# OpenTracker_GPS.net
KiCad netlist of a schematic drawn in EAGLE
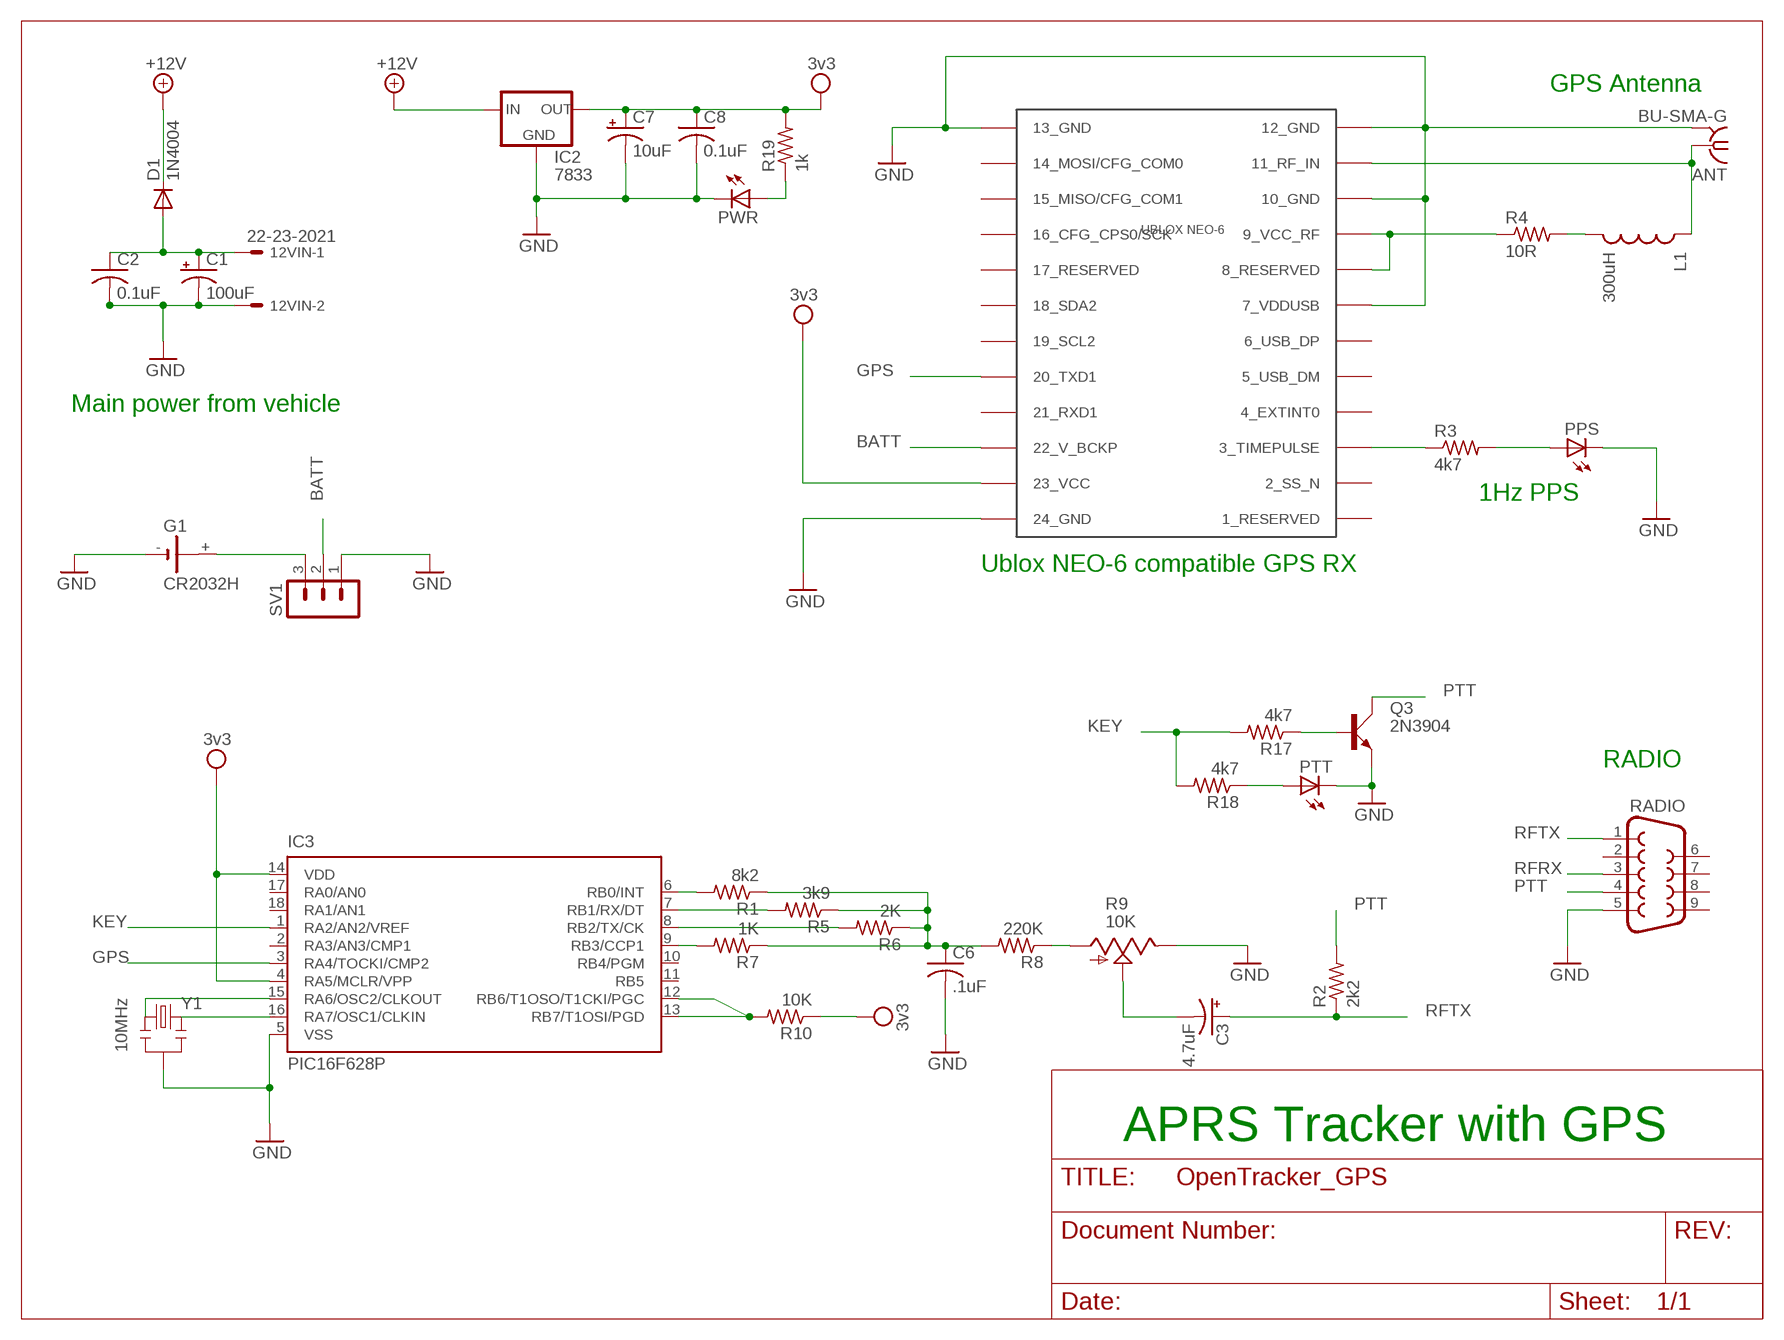
[diagram p0: schematic, sheet 1]

(export (version "E")
  (design (tool "Eeschema 10.0.6"))
  (components
    (comp (ref "12VIN")
      (value "22-23-2021")
      (footprint "eagle-import:22-23-2021")
      (fields (field (name "MF") "MOLEX"))
      (libsource (lib "eagle-import") (part "22-23-2021"))
    )
    (comp (ref "ANT")
      (value "BU-SMA-G")
      (footprint "eagle-import:BU-SMA-G")
      (libsource (lib "eagle-import") (part "BU-SMA-G"))
    )
    (comp (ref "C1")
      (value "100uF")
      (footprint "eagle-import:CPOL-RADIAL-10UF-25V")
      (libsource (lib "eagle-import") (part "CAP_POLPTH2"))
    )
    (comp (ref "C2")
      (value "0.1uF")
      (footprint "eagle-import:C025-025X050")
      (libsource (lib "eagle-import") (part "C-US025-025X050"))
    )
    (comp (ref "C3")
      (value "4.7uF")
      (footprint "eagle-import:CPOL-RADIAL-10UF-25V")
      (libsource (lib "eagle-import") (part "CAP_POLPTH2"))
    )
    (comp (ref "C6")
      (value ".1uF")
      (footprint "eagle-import:C025-025X050")
      (libsource (lib "eagle-import") (part "C-US025-025X050"))
    )
    (comp (ref "C7")
      (value "10uF")
      (footprint "eagle-import:CPOL-RADIAL-10UF-25V")
      (libsource (lib "eagle-import") (part "CAP_POLPTH2"))
    )
    (comp (ref "C8")
      (value "0.1uF")
      (footprint "eagle-import:C025-025X050")
      (libsource (lib "eagle-import") (part "C-US025-025X050"))
    )
    (comp (ref "D1")
      (value "1N4004")
      (footprint "eagle-import:DO41-10")
      (libsource (lib "eagle-import") (part "1N4004"))
    )
    (comp (ref "G1")
      (value "CR2032H")
      (footprint "eagle-import:CR2032H")
      (libsource (lib "eagle-import") (part "CR2032H"))
    )
    (comp (ref "IC2")
      (value "7833")
      (footprint "eagle-import:TO-220-ALT")
      (libsource (lib "eagle-import") (part "V_REG_78XX-TO-220"))
    )
    (comp (ref "IC3")
      (value "PIC16F628P")
      (footprint "eagle-import:DIL18")
      (libsource (lib "eagle-import") (part "PIC16F62P8"))
    )
    (comp (ref "L1")
      (value "300uH")
      (footprint "eagle-import:0805")
      (libsource (lib "eagle-import") (part "INDUCTOR0805"))
    )
    (comp (ref "PPS")
      (value "LED0603")
      (footprint "eagle-import:LED-0603")
      (libsource (lib "eagle-import") (part "LED0603"))
    )
    (comp (ref "PTT")
      (value "LED3MM")
      (footprint "eagle-import:LED3MM")
      (libsource (lib "eagle-import") (part "LED3MM"))
    )
    (comp (ref "PWR")
      (value "LED3MM")
      (footprint "eagle-import:LED3MM")
      (libsource (lib "eagle-import") (part "LED3MM"))
    )
    (comp (ref "Q3")
      (value "2N3904")
      (footprint "eagle-import:TO92D")
      (libsource (lib "eagle-import") (part "2N3904"))
    )
    (comp (ref "R1")
      (value "8k2")
      (footprint "eagle-import:0207_2V")
      (libsource (lib "eagle-import") (part "R-US_0207/2V"))
    )
    (comp (ref "R2")
      (value "2k2")
      (footprint "eagle-import:0207_2V")
      (libsource (lib "eagle-import") (part "R-US_0207/2V"))
    )
    (comp (ref "R3")
      (value "4k7")
      (footprint "eagle-import:M0805")
      (libsource (lib "eagle-import") (part "R-US_M0805"))
    )
    (comp (ref "R4")
      (value "10R")
      (footprint "eagle-import:M0805")
      (libsource (lib "eagle-import") (part "R-US_M0805"))
    )
    (comp (ref "R5")
      (value "3k9")
      (footprint "eagle-import:0207_2V")
      (libsource (lib "eagle-import") (part "R-US_0207/2V"))
    )
    (comp (ref "R6")
      (value "2K")
      (footprint "eagle-import:0207_2V")
      (libsource (lib "eagle-import") (part "R-US_0207/2V"))
    )
    (comp (ref "R7")
      (value "1K")
      (footprint "eagle-import:0207_2V")
      (libsource (lib "eagle-import") (part "R-US_0207/2V"))
    )
    (comp (ref "R8")
      (value "220K")
      (footprint "eagle-import:0207_2V")
      (libsource (lib "eagle-import") (part "R-US_0207/2V"))
    )
    (comp (ref "R9")
      (value "10K")
      (footprint "eagle-import:CA6V")
      (libsource (lib "eagle-import") (part "TRIM_US-CA6V"))
    )
    (comp (ref "R10")
      (value "10K")
      (footprint "eagle-import:0207_2V")
      (libsource (lib "eagle-import") (part "R-US_0207/2V"))
    )
    (comp (ref "R17")
      (value "4k7")
      (footprint "eagle-import:0207_2V")
      (libsource (lib "eagle-import") (part "R-US_0207/2V"))
    )
    (comp (ref "R18")
      (value "4k7")
      (footprint "eagle-import:0207_2V")
      (libsource (lib "eagle-import") (part "R-US_0207/2V"))
    )
    (comp (ref "R19")
      (value "1k")
      (footprint "eagle-import:0207_2V")
      (libsource (lib "eagle-import") (part "R-US_0207/2V"))
    )
    (comp (ref "RADIO")
      (value "F09HP")
      (footprint "eagle-import:F09HP")
      (libsource (lib "eagle-import") (part "F09HP"))
    )
    (comp (ref "SV1")
      (value "MA03-1")
      (footprint "eagle-import:MA03-1")
      (libsource (lib "eagle-import") (part "MA03-1"))
    )
    (comp (ref "U$1")
      (value "UBLOX_NEO-6")
      (footprint "eagle-import:UBLOX_NEO-6P")
      (libsource (lib "eagle-import") (part "UBLOX_NEO-6"))
    )
    (comp (ref "Y1")
      (value "10MHz")
      (footprint "eagle-import:RESONATOR-PTH")
      (libsource (lib "eagle-import") (part "RESONATORPTH"))
    )
  )
  (nets
    (net (code "1") (name "+12V") (class "Default")
      (node (ref "D1") (pin "C") (pinfunction "C_C") (pintype "passive"))
      (node (ref "IC2") (pin "IN") (pinfunction "IN_IN") (pintype "input"))
    )
    (net (code "2") (name "/BATT") (class "Default")
      (node (ref "SV1") (pin "2") (pinfunction "2_2") (pintype "passive"))
      (node (ref "U$1") (pin "22_V_BCKP") (pinfunction "22_V_BCKP_22_V_BCKP") (pintype "bidirectional"))
    )
    (net (code "3") (name "/GPS") (class "Default")
      (node (ref "IC3") (pin "3") (pinfunction "RA4/TOCKI/CMP2_3") (pintype "bidirectional"))
      (node (ref "U$1") (pin "20_TXD1") (pinfunction "20_TXD1_20_TXD1") (pintype "bidirectional"))
    )
    (net (code "4") (name "/KEY") (class "Default")
      (node (ref "IC3") (pin "1") (pinfunction "RA2/AN2/VREF_1") (pintype "bidirectional"))
      (node (ref "R17") (pin "2") (pinfunction "2_2") (pintype "passive"))
      (node (ref "R18") (pin "2") (pinfunction "2_2") (pintype "passive"))
    )
    (net (code "5") (name "/PTT") (class "Default")
      (node (ref "Q3") (pin "C") (pinfunction "C_C") (pintype "passive"))
      (node (ref "R2") (pin "2") (pinfunction "2_2") (pintype "passive"))
      (node (ref "RADIO") (pin "4") (pinfunction "4_4") (pintype "passive"))
    )
    (net (code "6") (name "/RFRX") (class "Default")
      (node (ref "RADIO") (pin "3") (pinfunction "3_3") (pintype "passive"))
    )
    (net (code "7") (name "/RFTX") (class "Default")
      (node (ref "C3") (pin "1") (pinfunction "+_1") (pintype "passive"))
      (node (ref "R2") (pin "1") (pinfunction "1_1") (pintype "passive"))
      (node (ref "RADIO") (pin "1") (pinfunction "1_1") (pintype "passive"))
    )
    (net (code "8") (name "3v3") (class "Default")
      (node (ref "C7") (pin "1") (pinfunction "+_1") (pintype "passive"))
      (node (ref "C8") (pin "1") (pinfunction "1_1") (pintype "passive"))
      (node (ref "IC2") (pin "OUT") (pinfunction "OUT_OUT") (pintype "output"))
      (node (ref "IC3") (pin "14") (pinfunction "VDD_14") (pintype "power_in"))
      (node (ref "IC3") (pin "4") (pinfunction "RA5/MCLR/VPP_4") (pintype "bidirectional"))
      (node (ref "R10") (pin "1") (pinfunction "1_1") (pintype "passive"))
      (node (ref "R19") (pin "2") (pinfunction "2_2") (pintype "passive"))
      (node (ref "U$1") (pin "23_VCC") (pinfunction "23_VCC_23_VCC") (pintype "bidirectional"))
    )
    (net (code "9") (name "GND") (class "Default")
      (node (ref "12VIN") (pin "2") (pinfunction "S_2") (pintype "passive"))
      (node (ref "ANT") (pin "2") (pinfunction "GND_2") (pintype "power_in"))
      (node (ref "C1") (pin "2") (pinfunction "-_2") (pintype "passive"))
      (node (ref "C2") (pin "2") (pinfunction "2_2") (pintype "passive"))
      (node (ref "C6") (pin "2") (pinfunction "2_2") (pintype "passive"))
      (node (ref "C7") (pin "2") (pinfunction "-_2") (pintype "passive"))
      (node (ref "C8") (pin "2") (pinfunction "2_2") (pintype "passive"))
      (node (ref "G1") (pin "-") (pinfunction "-_-") (pintype "passive"))
      (node (ref "IC2") (pin "GND") (pinfunction "GND_GND") (pintype "input"))
      (node (ref "IC3") (pin "5") (pinfunction "VSS_5") (pintype "power_in"))
      (node (ref "PPS") (pin "C") (pinfunction "C_C") (pintype "passive"))
      (node (ref "PTT") (pin "K") (pinfunction "C_K") (pintype "passive"))
      (node (ref "PWR") (pin "K") (pinfunction "C_K") (pintype "passive"))
      (node (ref "Q3") (pin "E") (pinfunction "E_E") (pintype "passive"))
      (node (ref "R9") (pin "E") (pinfunction "E_E") (pintype "passive"))
      (node (ref "RADIO") (pin "5") (pinfunction "5_5") (pintype "passive"))
      (node (ref "SV1") (pin "1") (pinfunction "1_1") (pintype "passive"))
      (node (ref "U$1") (pin "10_GND") (pinfunction "10_GND_10_GND") (pintype "bidirectional"))
      (node (ref "U$1") (pin "12_GND") (pinfunction "12_GND_12_GND") (pintype "bidirectional"))
      (node (ref "U$1") (pin "13_GND") (pinfunction "13_GND_13_GND") (pintype "bidirectional"))
      (node (ref "U$1") (pin "24_GND") (pinfunction "24_GND_24_GND") (pintype "bidirectional"))
      (node (ref "U$1") (pin "7_VDDUSB") (pinfunction "7_VDDUSB_7_VDDUSB") (pintype "bidirectional"))
      (node (ref "Y1") (pin "2") (pinfunction "2_2") (pintype "passive"))
    )
    (net (code "10") (name "Net-(12VINA-S)") (class "Default")
      (node (ref "12VIN") (pin "1") (pinfunction "S_1") (pintype "passive"))
      (node (ref "C1") (pin "1") (pinfunction "+_1") (pintype "passive"))
      (node (ref "C2") (pin "1") (pinfunction "1_1") (pintype "passive"))
      (node (ref "D1") (pin "A") (pinfunction "A_A") (pintype "passive"))
    )
    (net (code "11") (name "Net-(ANT-Pad1)") (class "Default")
      (node (ref "ANT") (pin "1") (pinfunction "1_1") (pintype "passive"))
      (node (ref "L1") (pin "1") (pinfunction "1_1") (pintype "passive"))
      (node (ref "U$1") (pin "11_RF_IN") (pinfunction "11_RF_IN_11_RF_IN") (pintype "bidirectional"))
    )
    (net (code "12") (name "Net-(C3--)") (class "Default")
      (node (ref "C3") (pin "2") (pinfunction "-_2") (pintype "passive"))
      (node (ref "R9") (pin "S") (pinfunction "S_S") (pintype "passive"))
    )
    (net (code "13") (name "Net-(C6-Pad1)") (class "Default")
      (node (ref "C6") (pin "1") (pinfunction "1_1") (pintype "passive"))
      (node (ref "R1") (pin "1") (pinfunction "1_1") (pintype "passive"))
      (node (ref "R5") (pin "1") (pinfunction "1_1") (pintype "passive"))
      (node (ref "R6") (pin "1") (pinfunction "1_1") (pintype "passive"))
      (node (ref "R7") (pin "1") (pinfunction "1_1") (pintype "passive"))
      (node (ref "R8") (pin "2") (pinfunction "2_2") (pintype "passive"))
    )
    (net (code "14") (name "Net-(G1-Pad+)") (class "Default")
      (node (ref "G1") (pin "+") (pinfunction "+_+") (pintype "passive"))
      (node (ref "SV1") (pin "3") (pinfunction "3_3") (pintype "passive"))
    )
    (net (code "15") (name "Net-(IC3-RA6{slash}OSC2{slash}CLKOUT)") (class "Default")
      (node (ref "IC3") (pin "15") (pinfunction "RA6/OSC2/CLKOUT_15") (pintype "bidirectional"))
      (node (ref "Y1") (pin "1") (pinfunction "1_1") (pintype "passive"))
    )
    (net (code "16") (name "Net-(IC3-RA7{slash}OSC1{slash}CLKIN)") (class "Default")
      (node (ref "IC3") (pin "16") (pinfunction "RA7/OSC1/CLKIN_16") (pintype "bidirectional"))
      (node (ref "Y1") (pin "3") (pinfunction "3_3") (pintype "passive"))
    )
    (net (code "17") (name "Net-(IC3-RB0{slash}INT)") (class "Default")
      (node (ref "IC3") (pin "6") (pinfunction "RB0/INT_6") (pintype "bidirectional"))
      (node (ref "R1") (pin "2") (pinfunction "2_2") (pintype "passive"))
    )
    (net (code "18") (name "Net-(IC3-RB1{slash}RX{slash}DT)") (class "Default")
      (node (ref "IC3") (pin "7") (pinfunction "RB1/RX/DT_7") (pintype "bidirectional"))
      (node (ref "R5") (pin "2") (pinfunction "2_2") (pintype "passive"))
    )
    (net (code "19") (name "Net-(IC3-RB2{slash}TX{slash}CK)") (class "Default")
      (node (ref "IC3") (pin "8") (pinfunction "RB2/TX/CK_8") (pintype "bidirectional"))
      (node (ref "R6") (pin "2") (pinfunction "2_2") (pintype "passive"))
    )
    (net (code "20") (name "Net-(IC3-RB3{slash}CCP1)") (class "Default")
      (node (ref "IC3") (pin "9") (pinfunction "RB3/CCP1_9") (pintype "bidirectional"))
      (node (ref "R7") (pin "2") (pinfunction "2_2") (pintype "passive"))
    )
    (net (code "21") (name "Net-(IC3-RB6{slash}T1OSO{slash}T1CKI{slash}PGC)") (class "Default")
      (node (ref "IC3") (pin "12") (pinfunction "RB6/T1OSO/T1CKI/PGC_12") (pintype "bidirectional"))
      (node (ref "IC3") (pin "13") (pinfunction "RB7/T1OSI/PGD_13") (pintype "bidirectional"))
      (node (ref "R10") (pin "2") (pinfunction "2_2") (pintype "passive"))
    )
    (net (code "22") (name "Net-(L1-Pad2)") (class "Default")
      (node (ref "L1") (pin "2") (pinfunction "2_2") (pintype "passive"))
      (node (ref "R4") (pin "2") (pinfunction "2_2") (pintype "passive"))
    )
    (net (code "23") (name "Net-(PPS-PadA)") (class "Default")
      (node (ref "PPS") (pin "A") (pinfunction "A_A") (pintype "passive"))
      (node (ref "R3") (pin "2") (pinfunction "2_2") (pintype "passive"))
    )
    (net (code "24") (name "Net-(PTT-PadA)") (class "Default")
      (node (ref "PTT") (pin "A") (pinfunction "A_A") (pintype "passive"))
      (node (ref "R18") (pin "1") (pinfunction "1_1") (pintype "passive"))
    )
    (net (code "25") (name "Net-(PWR-PadA)") (class "Default")
      (node (ref "PWR") (pin "A") (pinfunction "A_A") (pintype "passive"))
      (node (ref "R19") (pin "1") (pinfunction "1_1") (pintype "passive"))
    )
    (net (code "26") (name "Net-(Q3-PadB)") (class "Default")
      (node (ref "Q3") (pin "B") (pinfunction "B_B") (pintype "passive"))
      (node (ref "R17") (pin "1") (pinfunction "1_1") (pintype "passive"))
    )
    (net (code "27") (name "Net-(R3-Pad1)") (class "Default")
      (node (ref "R3") (pin "1") (pinfunction "1_1") (pintype "passive"))
      (node (ref "U$1") (pin "3_TIMEPULSE") (pinfunction "3_TIMEPULSE_3_TIMEPULSE") (pintype "bidirectional"))
    )
    (net (code "28") (name "Net-(R4-Pad1)") (class "Default")
      (node (ref "R4") (pin "1") (pinfunction "1_1") (pintype "passive"))
      (node (ref "U$1") (pin "8_RESERVED") (pinfunction "8_RESERVED_8_RESERVED") (pintype "bidirectional"))
      (node (ref "U$1") (pin "9_VCC_RF") (pinfunction "9_VCC_RF_9_VCC_RF") (pintype "bidirectional"))
    )
    (net (code "29") (name "Net-(R8-Pad1)") (class "Default")
      (node (ref "R8") (pin "1") (pinfunction "1_1") (pintype "passive"))
      (node (ref "R9") (pin "A") (pinfunction "A_A") (pintype "passive"))
    )
    (net (code "30") (name "unconnected-(G1-+-Pad+@1)") (class "Default")
      (node (ref "G1") (pin "+@1") (pinfunction "+_+@1") (pintype "passive"))
    )
    (net (code "31") (name "unconnected-(IC3-RA0{slash}AN0-Pad17)") (class "Default")
      (node (ref "IC3") (pin "17") (pinfunction "RA0/AN0_17") (pintype "bidirectional"))
    )
    (net (code "32") (name "unconnected-(IC3-RA1{slash}AN1-Pad18)") (class "Default")
      (node (ref "IC3") (pin "18") (pinfunction "RA1/AN1_18") (pintype "bidirectional"))
    )
    (net (code "33") (name "unconnected-(IC3-RA3{slash}AN3{slash}CMP1-Pad2)") (class "Default")
      (node (ref "IC3") (pin "2") (pinfunction "RA3/AN3/CMP1_2") (pintype "bidirectional"))
    )
    (net (code "34") (name "unconnected-(IC3-RB4{slash}PGM-Pad10)") (class "Default")
      (node (ref "IC3") (pin "10") (pinfunction "RB4/PGM_10") (pintype "bidirectional"))
    )
    (net (code "35") (name "unconnected-(IC3-RB5-Pad11)") (class "Default")
      (node (ref "IC3") (pin "11") (pinfunction "RB5_11") (pintype "bidirectional"))
    )
    (net (code "36") (name "unconnected-(RADIO-Pad2)") (class "Default")
      (node (ref "RADIO") (pin "2") (pinfunction "2_2") (pintype "passive"))
    )
    (net (code "37") (name "unconnected-(RADIO-Pad6)") (class "Default")
      (node (ref "RADIO") (pin "6") (pinfunction "6_6") (pintype "passive"))
    )
    (net (code "38") (name "unconnected-(RADIO-Pad7)") (class "Default")
      (node (ref "RADIO") (pin "7") (pinfunction "7_7") (pintype "passive"))
    )
    (net (code "39") (name "unconnected-(RADIO-Pad8)") (class "Default")
      (node (ref "RADIO") (pin "8") (pinfunction "8_8") (pintype "passive"))
    )
    (net (code "40") (name "unconnected-(RADIO-Pad9)") (class "Default")
      (node (ref "RADIO") (pin "9") (pinfunction "9_9") (pintype "passive"))
    )
    (net (code "41") (name "unconnected-(U$1-Pad1_RESERVED)") (class "Default")
      (node (ref "U$1") (pin "1_RESERVED") (pinfunction "1_RESERVED_1_RESERVED") (pintype "bidirectional"))
    )
    (net (code "42") (name "unconnected-(U$1-Pad2_SS_N)") (class "Default")
      (node (ref "U$1") (pin "2_SS_N") (pinfunction "2_SS_N_2_SS_N") (pintype "bidirectional"))
    )
    (net (code "43") (name "unconnected-(U$1-Pad4_EXTINT0)") (class "Default")
      (node (ref "U$1") (pin "4_EXTINT0") (pinfunction "4_EXTINT0_4_EXTINT0") (pintype "bidirectional"))
    )
    (net (code "44") (name "unconnected-(U$1-Pad5_USB_DM)") (class "Default")
      (node (ref "U$1") (pin "5_USB_DM") (pinfunction "5_USB_DM_5_USB_DM") (pintype "bidirectional"))
    )
    (net (code "45") (name "unconnected-(U$1-Pad6_USB_DP)") (class "Default")
      (node (ref "U$1") (pin "6_USB_DP") (pinfunction "6_USB_DP_6_USB_DP") (pintype "bidirectional"))
    )
    (net (code "46") (name "unconnected-(U$1-Pad14_MOSI{slash}CFG_COM0)") (class "Default")
      (node (ref "U$1") (pin "14_MOSI/CFG_COM0") (pinfunction "14_MOSI/CFG_COM0_14_MOSI/CFG_COM0") (pintype "bidirectional"))
    )
    (net (code "47") (name "unconnected-(U$1-Pad15_MISO{slash}CFG_COM1)") (class "Default")
      (node (ref "U$1") (pin "15_MISO/CFG_COM1") (pinfunction "15_MISO/CFG_COM1_15_MISO/CFG_COM1") (pintype "bidirectional"))
    )
    (net (code "48") (name "unconnected-(U$1-Pad16_CFG_CPS0{slash}SCK)") (class "Default")
      (node (ref "U$1") (pin "16_CFG_CPS0/SCK") (pinfunction "16_CFG_CPS0/SCK_16_CFG_CPS0/SCK") (pintype "bidirectional"))
    )
    (net (code "49") (name "unconnected-(U$1-Pad17_RESERVED)") (class "Default")
      (node (ref "U$1") (pin "17_RESERVED") (pinfunction "17_RESERVED_17_RESERVED") (pintype "bidirectional"))
    )
    (net (code "50") (name "unconnected-(U$1-Pad18_SDA2)") (class "Default")
      (node (ref "U$1") (pin "18_SDA2") (pinfunction "18_SDA2_18_SDA2") (pintype "bidirectional"))
    )
    (net (code "51") (name "unconnected-(U$1-Pad19_SCL2)") (class "Default")
      (node (ref "U$1") (pin "19_SCL2") (pinfunction "19_SCL2_19_SCL2") (pintype "bidirectional"))
    )
    (net (code "52") (name "unconnected-(U$1-Pad21_RXD1)") (class "Default")
      (node (ref "U$1") (pin "21_RXD1") (pinfunction "21_RXD1_21_RXD1") (pintype "bidirectional"))
    )
  )
)
